# FPGA_NonIO.net
KiCad netlist of a schematic drawn in Altium Designer
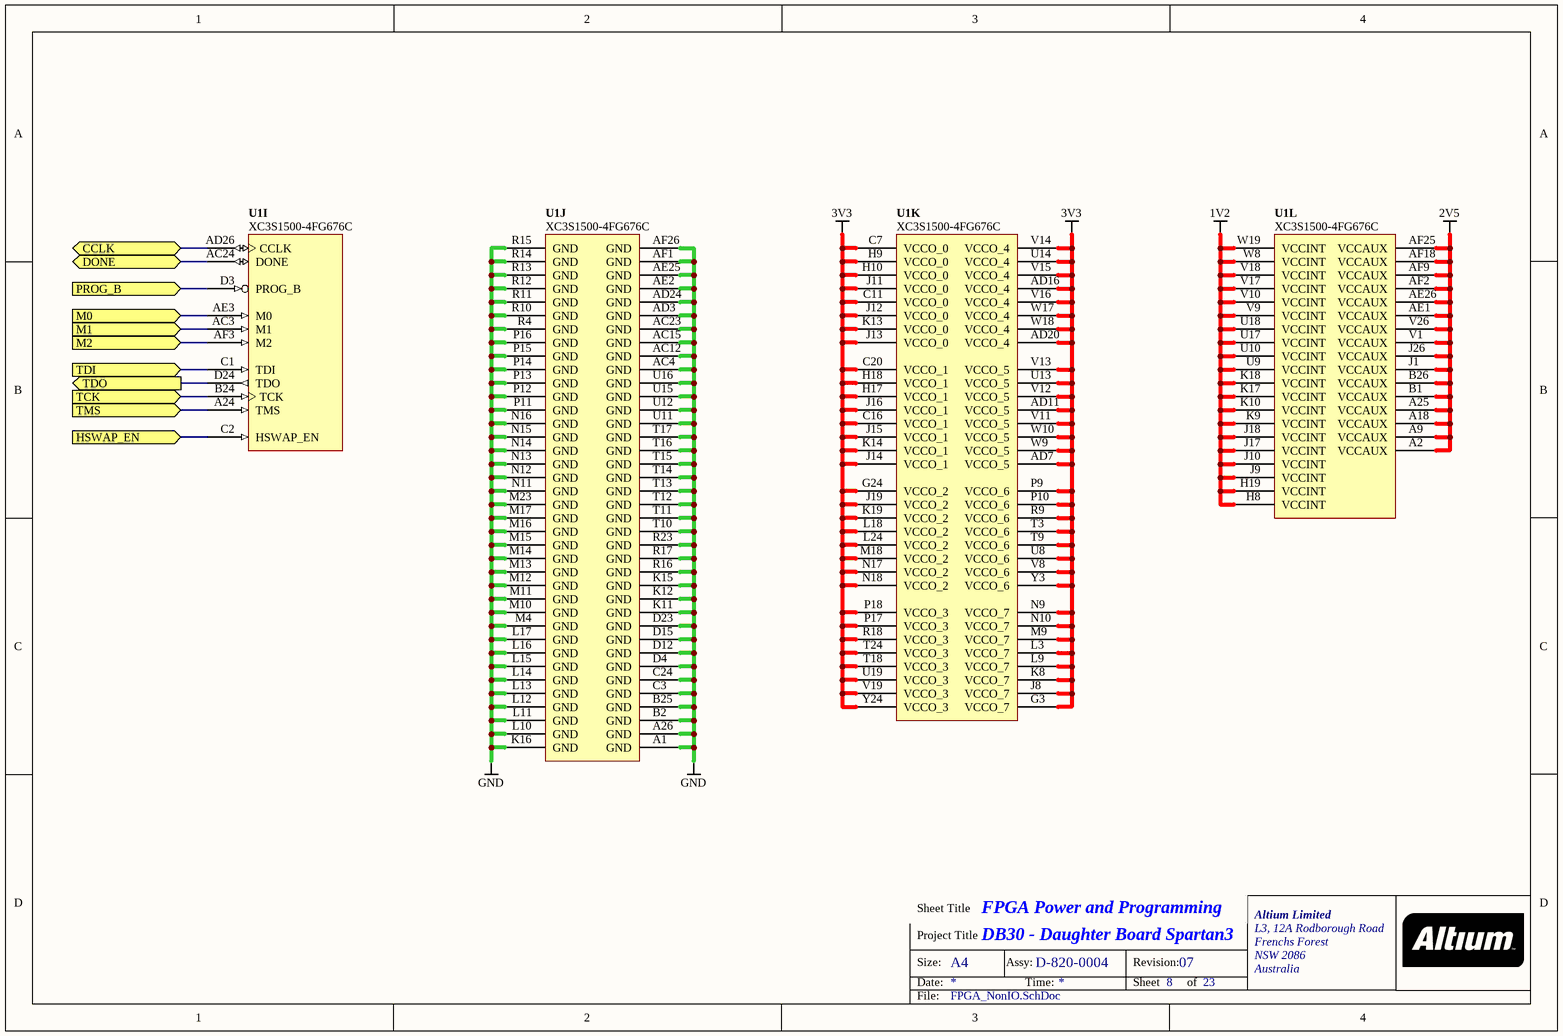
[diagram p0: FPGA_NonIO.SchDoc]

(export (version "E")
  (design (tool "Eeschema 10.0.6"))
  (components
    (comp (ref "U1")
      (value "XC3S1500-4FG676C")
      (footprint "BGA100P26X26-676")
      (description "FPGA, Xilinx Spartan3-1500 FG676 Speed=4")
      (libsource (lib "") (part "XC3S1500-4FG676C_1"))
    )
  )
  (nets
    (net (code "1") (name "/CCLK") (class "Default")
      (node (ref "U1") (pin "AD26") (pinfunction "CCLK_AD26") (pintype "bidirectional"))
    )
    (net (code "2") (name "/DONE") (class "Default")
      (node (ref "U1") (pin "AC24") (pinfunction "DONE_AC24") (pintype "bidirectional"))
    )
    (net (code "3") (name "/HSWAP_EN") (class "Default")
      (node (ref "U1") (pin "C2") (pinfunction "HSWAP_EN_C2") (pintype "input"))
    )
    (net (code "4") (name "/M0") (class "Default")
      (node (ref "U1") (pin "AE3") (pinfunction "M0_AE3") (pintype "input"))
    )
    (net (code "5") (name "/M1") (class "Default")
      (node (ref "U1") (pin "AC3") (pinfunction "M1_AC3") (pintype "input"))
    )
    (net (code "6") (name "/M2") (class "Default")
      (node (ref "U1") (pin "AF3") (pinfunction "M2_AF3") (pintype "input"))
    )
    (net (code "7") (name "/PROG_B") (class "Default")
      (node (ref "U1") (pin "D3") (pinfunction "PROG_B_D3") (pintype "input"))
    )
    (net (code "8") (name "/TCK") (class "Default")
      (node (ref "U1") (pin "B24") (pinfunction "TCK_B24") (pintype "input"))
    )
    (net (code "9") (name "/TDI") (class "Default")
      (node (ref "U1") (pin "C1") (pinfunction "TDI_C1") (pintype "input"))
    )
    (net (code "10") (name "/TDO") (class "Default")
      (node (ref "U1") (pin "D24") (pinfunction "TDO_D24") (pintype "output"))
    )
    (net (code "11") (name "/TMS") (class "Default")
      (node (ref "U1") (pin "A24") (pinfunction "TMS_A24") (pintype "input"))
    )
    (net (code "12") (name "1V2") (class "Default")
      (node (ref "U1") (pin "H19") (pinfunction "VCCINT_H19") (pintype "power_in"))
      (node (ref "U1") (pin "H8") (pinfunction "VCCINT_H8") (pintype "power_in"))
      (node (ref "U1") (pin "J10") (pinfunction "VCCINT_J10") (pintype "power_in"))
      (node (ref "U1") (pin "J17") (pinfunction "VCCINT_J17") (pintype "power_in"))
      (node (ref "U1") (pin "J18") (pinfunction "VCCINT_J18") (pintype "power_in"))
      (node (ref "U1") (pin "J9") (pinfunction "VCCINT_J9") (pintype "power_in"))
      (node (ref "U1") (pin "K10") (pinfunction "VCCINT_K10") (pintype "power_in"))
      (node (ref "U1") (pin "K17") (pinfunction "VCCINT_K17") (pintype "power_in"))
      (node (ref "U1") (pin "K18") (pinfunction "VCCINT_K18") (pintype "power_in"))
      (node (ref "U1") (pin "K9") (pinfunction "VCCINT_K9") (pintype "power_in"))
      (node (ref "U1") (pin "U10") (pinfunction "VCCINT_U10") (pintype "power_in"))
      (node (ref "U1") (pin "U17") (pinfunction "VCCINT_U17") (pintype "power_in"))
      (node (ref "U1") (pin "U18") (pinfunction "VCCINT_U18") (pintype "power_in"))
      (node (ref "U1") (pin "U9") (pinfunction "VCCINT_U9") (pintype "power_in"))
      (node (ref "U1") (pin "V10") (pinfunction "VCCINT_V10") (pintype "power_in"))
      (node (ref "U1") (pin "V17") (pinfunction "VCCINT_V17") (pintype "power_in"))
      (node (ref "U1") (pin "V18") (pinfunction "VCCINT_V18") (pintype "power_in"))
      (node (ref "U1") (pin "V9") (pinfunction "VCCINT_V9") (pintype "power_in"))
      (node (ref "U1") (pin "W19") (pinfunction "VCCINT_W19") (pintype "power_in"))
      (node (ref "U1") (pin "W8") (pinfunction "VCCINT_W8") (pintype "power_in"))
    )
    (net (code "13") (name "2V5") (class "Default")
      (node (ref "U1") (pin "A18") (pinfunction "VCCAUX_A18") (pintype "power_in"))
      (node (ref "U1") (pin "A2") (pinfunction "VCCAUX_A2") (pintype "power_in"))
      (node (ref "U1") (pin "A25") (pinfunction "VCCAUX_A25") (pintype "power_in"))
      (node (ref "U1") (pin "A9") (pinfunction "VCCAUX_A9") (pintype "power_in"))
      (node (ref "U1") (pin "AE1") (pinfunction "VCCAUX_AE1") (pintype "power_in"))
      (node (ref "U1") (pin "AE26") (pinfunction "VCCAUX_AE26") (pintype "power_in"))
      (node (ref "U1") (pin "AF18") (pinfunction "VCCAUX_AF18") (pintype "power_in"))
      (node (ref "U1") (pin "AF2") (pinfunction "VCCAUX_AF2") (pintype "power_in"))
      (node (ref "U1") (pin "AF25") (pinfunction "VCCAUX_AF25") (pintype "power_in"))
      (node (ref "U1") (pin "AF9") (pinfunction "VCCAUX_AF9") (pintype "power_in"))
      (node (ref "U1") (pin "B1") (pinfunction "VCCAUX_B1") (pintype "power_in"))
      (node (ref "U1") (pin "B26") (pinfunction "VCCAUX_B26") (pintype "power_in"))
      (node (ref "U1") (pin "J1") (pinfunction "VCCAUX_J1") (pintype "power_in"))
      (node (ref "U1") (pin "J26") (pinfunction "VCCAUX_J26") (pintype "power_in"))
      (node (ref "U1") (pin "V1") (pinfunction "VCCAUX_V1") (pintype "power_in"))
      (node (ref "U1") (pin "V26") (pinfunction "VCCAUX_V26") (pintype "power_in"))
    )
    (net (code "14") (name "3V3") (class "Default")
      (node (ref "U1") (pin "AD11") (pinfunction "VCCO_5_AD11") (pintype "power_in"))
      (node (ref "U1") (pin "AD16") (pinfunction "VCCO_4_AD16") (pintype "power_in"))
      (node (ref "U1") (pin "AD20") (pinfunction "VCCO_4_AD20") (pintype "power_in"))
      (node (ref "U1") (pin "AD7") (pinfunction "VCCO_5_AD7") (pintype "power_in"))
      (node (ref "U1") (pin "C11") (pinfunction "VCCO_0_C11") (pintype "power_in"))
      (node (ref "U1") (pin "C16") (pinfunction "VCCO_1_C16") (pintype "power_in"))
      (node (ref "U1") (pin "C20") (pinfunction "VCCO_1_C20") (pintype "power_in"))
      (node (ref "U1") (pin "C7") (pinfunction "VCCO_0_C7") (pintype "power_in"))
      (node (ref "U1") (pin "G24") (pinfunction "VCCO_2_G24") (pintype "power_in"))
      (node (ref "U1") (pin "G3") (pinfunction "VCCO_7_G3") (pintype "power_in"))
      (node (ref "U1") (pin "H10") (pinfunction "VCCO_0_H10") (pintype "power_in"))
      (node (ref "U1") (pin "H17") (pinfunction "VCCO_1_H17") (pintype "power_in"))
      (node (ref "U1") (pin "H18") (pinfunction "VCCO_1_H18") (pintype "power_in"))
      (node (ref "U1") (pin "H9") (pinfunction "VCCO_0_H9") (pintype "power_in"))
      (node (ref "U1") (pin "J11") (pinfunction "VCCO_0_J11") (pintype "power_in"))
      (node (ref "U1") (pin "J12") (pinfunction "VCCO_0_J12") (pintype "power_in"))
      (node (ref "U1") (pin "J13") (pinfunction "VCCO_0_J13") (pintype "power_in"))
      (node (ref "U1") (pin "J14") (pinfunction "VCCO_1_J14") (pintype "power_in"))
      (node (ref "U1") (pin "J15") (pinfunction "VCCO_1_J15") (pintype "power_in"))
      (node (ref "U1") (pin "J16") (pinfunction "VCCO_1_J16") (pintype "power_in"))
      (node (ref "U1") (pin "J19") (pinfunction "VCCO_2_J19") (pintype "power_in"))
      (node (ref "U1") (pin "J8") (pinfunction "VCCO_7_J8") (pintype "power_in"))
      (node (ref "U1") (pin "K13") (pinfunction "VCCO_0_K13") (pintype "power_in"))
      (node (ref "U1") (pin "K14") (pinfunction "VCCO_1_K14") (pintype "power_in"))
      (node (ref "U1") (pin "K19") (pinfunction "VCCO_2_K19") (pintype "power_in"))
      (node (ref "U1") (pin "K8") (pinfunction "VCCO_7_K8") (pintype "power_in"))
      (node (ref "U1") (pin "L18") (pinfunction "VCCO_2_L18") (pintype "power_in"))
      (node (ref "U1") (pin "L24") (pinfunction "VCCO_2_L24") (pintype "power_in"))
      (node (ref "U1") (pin "L3") (pinfunction "VCCO_7_L3") (pintype "power_in"))
      (node (ref "U1") (pin "L9") (pinfunction "VCCO_7_L9") (pintype "power_in"))
      (node (ref "U1") (pin "M18") (pinfunction "VCCO_2_M18") (pintype "power_in"))
      (node (ref "U1") (pin "M9") (pinfunction "VCCO_7_M9") (pintype "power_in"))
      (node (ref "U1") (pin "N10") (pinfunction "VCCO_7_N10") (pintype "power_in"))
      (node (ref "U1") (pin "N17") (pinfunction "VCCO_2_N17") (pintype "power_in"))
      (node (ref "U1") (pin "N18") (pinfunction "VCCO_2_N18") (pintype "power_in"))
      (node (ref "U1") (pin "N9") (pinfunction "VCCO_7_N9") (pintype "power_in"))
      (node (ref "U1") (pin "P10") (pinfunction "VCCO_6_P10") (pintype "power_in"))
      (node (ref "U1") (pin "P17") (pinfunction "VCCO_3_P17") (pintype "power_in"))
      (node (ref "U1") (pin "P18") (pinfunction "VCCO_3_P18") (pintype "power_in"))
      (node (ref "U1") (pin "P9") (pinfunction "VCCO_6_P9") (pintype "power_in"))
      (node (ref "U1") (pin "R18") (pinfunction "VCCO_3_R18") (pintype "power_in"))
      (node (ref "U1") (pin "R9") (pinfunction "VCCO_6_R9") (pintype "power_in"))
      (node (ref "U1") (pin "T18") (pinfunction "VCCO_3_T18") (pintype "power_in"))
      (node (ref "U1") (pin "T24") (pinfunction "VCCO_3_T24") (pintype "power_in"))
      (node (ref "U1") (pin "T3") (pinfunction "VCCO_6_T3") (pintype "power_in"))
      (node (ref "U1") (pin "T9") (pinfunction "VCCO_6_T9") (pintype "power_in"))
      (node (ref "U1") (pin "U13") (pinfunction "VCCO_5_U13") (pintype "power_in"))
      (node (ref "U1") (pin "U14") (pinfunction "VCCO_4_U14") (pintype "power_in"))
      (node (ref "U1") (pin "U19") (pinfunction "VCCO_3_U19") (pintype "power_in"))
      (node (ref "U1") (pin "U8") (pinfunction "VCCO_6_U8") (pintype "power_in"))
      (node (ref "U1") (pin "V11") (pinfunction "VCCO_5_V11") (pintype "power_in"))
      (node (ref "U1") (pin "V12") (pinfunction "VCCO_5_V12") (pintype "power_in"))
      (node (ref "U1") (pin "V13") (pinfunction "VCCO_5_V13") (pintype "power_in"))
      (node (ref "U1") (pin "V14") (pinfunction "VCCO_4_V14") (pintype "power_in"))
      (node (ref "U1") (pin "V15") (pinfunction "VCCO_4_V15") (pintype "power_in"))
      (node (ref "U1") (pin "V16") (pinfunction "VCCO_4_V16") (pintype "power_in"))
      (node (ref "U1") (pin "V19") (pinfunction "VCCO_3_V19") (pintype "power_in"))
      (node (ref "U1") (pin "V8") (pinfunction "VCCO_6_V8") (pintype "power_in"))
      (node (ref "U1") (pin "W10") (pinfunction "VCCO_5_W10") (pintype "power_in"))
      (node (ref "U1") (pin "W17") (pinfunction "VCCO_4_W17") (pintype "power_in"))
      (node (ref "U1") (pin "W18") (pinfunction "VCCO_4_W18") (pintype "power_in"))
      (node (ref "U1") (pin "W9") (pinfunction "VCCO_5_W9") (pintype "power_in"))
      (node (ref "U1") (pin "Y24") (pinfunction "VCCO_3_Y24") (pintype "power_in"))
      (node (ref "U1") (pin "Y3") (pinfunction "VCCO_6_Y3") (pintype "power_in"))
    )
    (net (code "15") (name "GND") (class "Default")
      (node (ref "U1") (pin "A1") (pinfunction "GND_A1") (pintype "power_in"))
      (node (ref "U1") (pin "A26") (pinfunction "GND_A26") (pintype "power_in"))
      (node (ref "U1") (pin "AC12") (pinfunction "GND_AC12") (pintype "power_in"))
      (node (ref "U1") (pin "AC15") (pinfunction "GND_AC15") (pintype "power_in"))
      (node (ref "U1") (pin "AC23") (pinfunction "GND_AC23") (pintype "power_in"))
      (node (ref "U1") (pin "AC4") (pinfunction "GND_AC4") (pintype "power_in"))
      (node (ref "U1") (pin "AD24") (pinfunction "GND_AD24") (pintype "power_in"))
      (node (ref "U1") (pin "AD3") (pinfunction "GND_AD3") (pintype "power_in"))
      (node (ref "U1") (pin "AE2") (pinfunction "GND_AE2") (pintype "power_in"))
      (node (ref "U1") (pin "AE25") (pinfunction "GND_AE25") (pintype "power_in"))
      (node (ref "U1") (pin "AF1") (pinfunction "GND_AF1") (pintype "power_in"))
      (node (ref "U1") (pin "AF26") (pinfunction "GND_AF26") (pintype "power_in"))
      (node (ref "U1") (pin "B2") (pinfunction "GND_B2") (pintype "power_in"))
      (node (ref "U1") (pin "B25") (pinfunction "GND_B25") (pintype "power_in"))
      (node (ref "U1") (pin "C24") (pinfunction "GND_C24") (pintype "power_in"))
      (node (ref "U1") (pin "C3") (pinfunction "GND_C3") (pintype "power_in"))
      (node (ref "U1") (pin "D12") (pinfunction "GND_D12") (pintype "power_in"))
      (node (ref "U1") (pin "D15") (pinfunction "GND_D15") (pintype "power_in"))
      (node (ref "U1") (pin "D23") (pinfunction "GND_D23") (pintype "power_in"))
      (node (ref "U1") (pin "D4") (pinfunction "GND_D4") (pintype "power_in"))
      (node (ref "U1") (pin "K11") (pinfunction "GND_K11") (pintype "power_in"))
      (node (ref "U1") (pin "K12") (pinfunction "GND_K12") (pintype "power_in"))
      (node (ref "U1") (pin "K15") (pinfunction "GND_K15") (pintype "power_in"))
      (node (ref "U1") (pin "K16") (pinfunction "GND_K16") (pintype "power_in"))
      (node (ref "U1") (pin "L10") (pinfunction "GND_L10") (pintype "power_in"))
      (node (ref "U1") (pin "L11") (pinfunction "GND_L11") (pintype "power_in"))
      (node (ref "U1") (pin "L12") (pinfunction "GND_L12") (pintype "power_in"))
      (node (ref "U1") (pin "L13") (pinfunction "GND_L13") (pintype "power_in"))
      (node (ref "U1") (pin "L14") (pinfunction "GND_L14") (pintype "power_in"))
      (node (ref "U1") (pin "L15") (pinfunction "GND_L15") (pintype "power_in"))
      (node (ref "U1") (pin "L16") (pinfunction "GND_L16") (pintype "power_in"))
      (node (ref "U1") (pin "L17") (pinfunction "GND_L17") (pintype "power_in"))
      (node (ref "U1") (pin "M10") (pinfunction "GND_M10") (pintype "power_in"))
      (node (ref "U1") (pin "M11") (pinfunction "GND_M11") (pintype "power_in"))
      (node (ref "U1") (pin "M12") (pinfunction "GND_M12") (pintype "power_in"))
      (node (ref "U1") (pin "M13") (pinfunction "GND_M13") (pintype "power_in"))
      (node (ref "U1") (pin "M14") (pinfunction "GND_M14") (pintype "power_in"))
      (node (ref "U1") (pin "M15") (pinfunction "GND_M15") (pintype "power_in"))
      (node (ref "U1") (pin "M16") (pinfunction "GND_M16") (pintype "power_in"))
      (node (ref "U1") (pin "M17") (pinfunction "GND_M17") (pintype "power_in"))
      (node (ref "U1") (pin "M23") (pinfunction "GND_M23") (pintype "power_in"))
      (node (ref "U1") (pin "M4") (pinfunction "GND_M4") (pintype "power_in"))
      (node (ref "U1") (pin "N11") (pinfunction "GND_N11") (pintype "power_in"))
      (node (ref "U1") (pin "N12") (pinfunction "GND_N12") (pintype "power_in"))
      (node (ref "U1") (pin "N13") (pinfunction "GND_N13") (pintype "power_in"))
      (node (ref "U1") (pin "N14") (pinfunction "GND_N14") (pintype "power_in"))
      (node (ref "U1") (pin "N15") (pinfunction "GND_N15") (pintype "power_in"))
      (node (ref "U1") (pin "N16") (pinfunction "GND_N16") (pintype "power_in"))
      (node (ref "U1") (pin "P11") (pinfunction "GND_P11") (pintype "power_in"))
      (node (ref "U1") (pin "P12") (pinfunction "GND_P12") (pintype "power_in"))
      (node (ref "U1") (pin "P13") (pinfunction "GND_P13") (pintype "power_in"))
      (node (ref "U1") (pin "P14") (pinfunction "GND_P14") (pintype "power_in"))
      (node (ref "U1") (pin "P15") (pinfunction "GND_P15") (pintype "power_in"))
      (node (ref "U1") (pin "P16") (pinfunction "GND_P16") (pintype "power_in"))
      (node (ref "U1") (pin "R10") (pinfunction "GND_R10") (pintype "power_in"))
      (node (ref "U1") (pin "R11") (pinfunction "GND_R11") (pintype "power_in"))
      (node (ref "U1") (pin "R12") (pinfunction "GND_R12") (pintype "power_in"))
      (node (ref "U1") (pin "R13") (pinfunction "GND_R13") (pintype "power_in"))
      (node (ref "U1") (pin "R14") (pinfunction "GND_R14") (pintype "power_in"))
      (node (ref "U1") (pin "R15") (pinfunction "GND_R15") (pintype "power_in"))
      (node (ref "U1") (pin "R16") (pinfunction "GND_R16") (pintype "power_in"))
      (node (ref "U1") (pin "R17") (pinfunction "GND_R17") (pintype "power_in"))
      (node (ref "U1") (pin "R23") (pinfunction "GND_R23") (pintype "power_in"))
      (node (ref "U1") (pin "R4") (pinfunction "GND_R4") (pintype "power_in"))
      (node (ref "U1") (pin "T10") (pinfunction "GND_T10") (pintype "power_in"))
      (node (ref "U1") (pin "T11") (pinfunction "GND_T11") (pintype "power_in"))
      (node (ref "U1") (pin "T12") (pinfunction "GND_T12") (pintype "power_in"))
      (node (ref "U1") (pin "T13") (pinfunction "GND_T13") (pintype "power_in"))
      (node (ref "U1") (pin "T14") (pinfunction "GND_T14") (pintype "power_in"))
      (node (ref "U1") (pin "T15") (pinfunction "GND_T15") (pintype "power_in"))
      (node (ref "U1") (pin "T16") (pinfunction "GND_T16") (pintype "power_in"))
      (node (ref "U1") (pin "T17") (pinfunction "GND_T17") (pintype "power_in"))
      (node (ref "U1") (pin "U11") (pinfunction "GND_U11") (pintype "power_in"))
      (node (ref "U1") (pin "U12") (pinfunction "GND_U12") (pintype "power_in"))
      (node (ref "U1") (pin "U15") (pinfunction "GND_U15") (pintype "power_in"))
      (node (ref "U1") (pin "U16") (pinfunction "GND_U16") (pintype "power_in"))
    )
  )
)
